# AIRZAI_LED_STRIP_FLEX_REVA_10mmPitch.net
KiCad netlist of a schematic drawn in Altium Designer
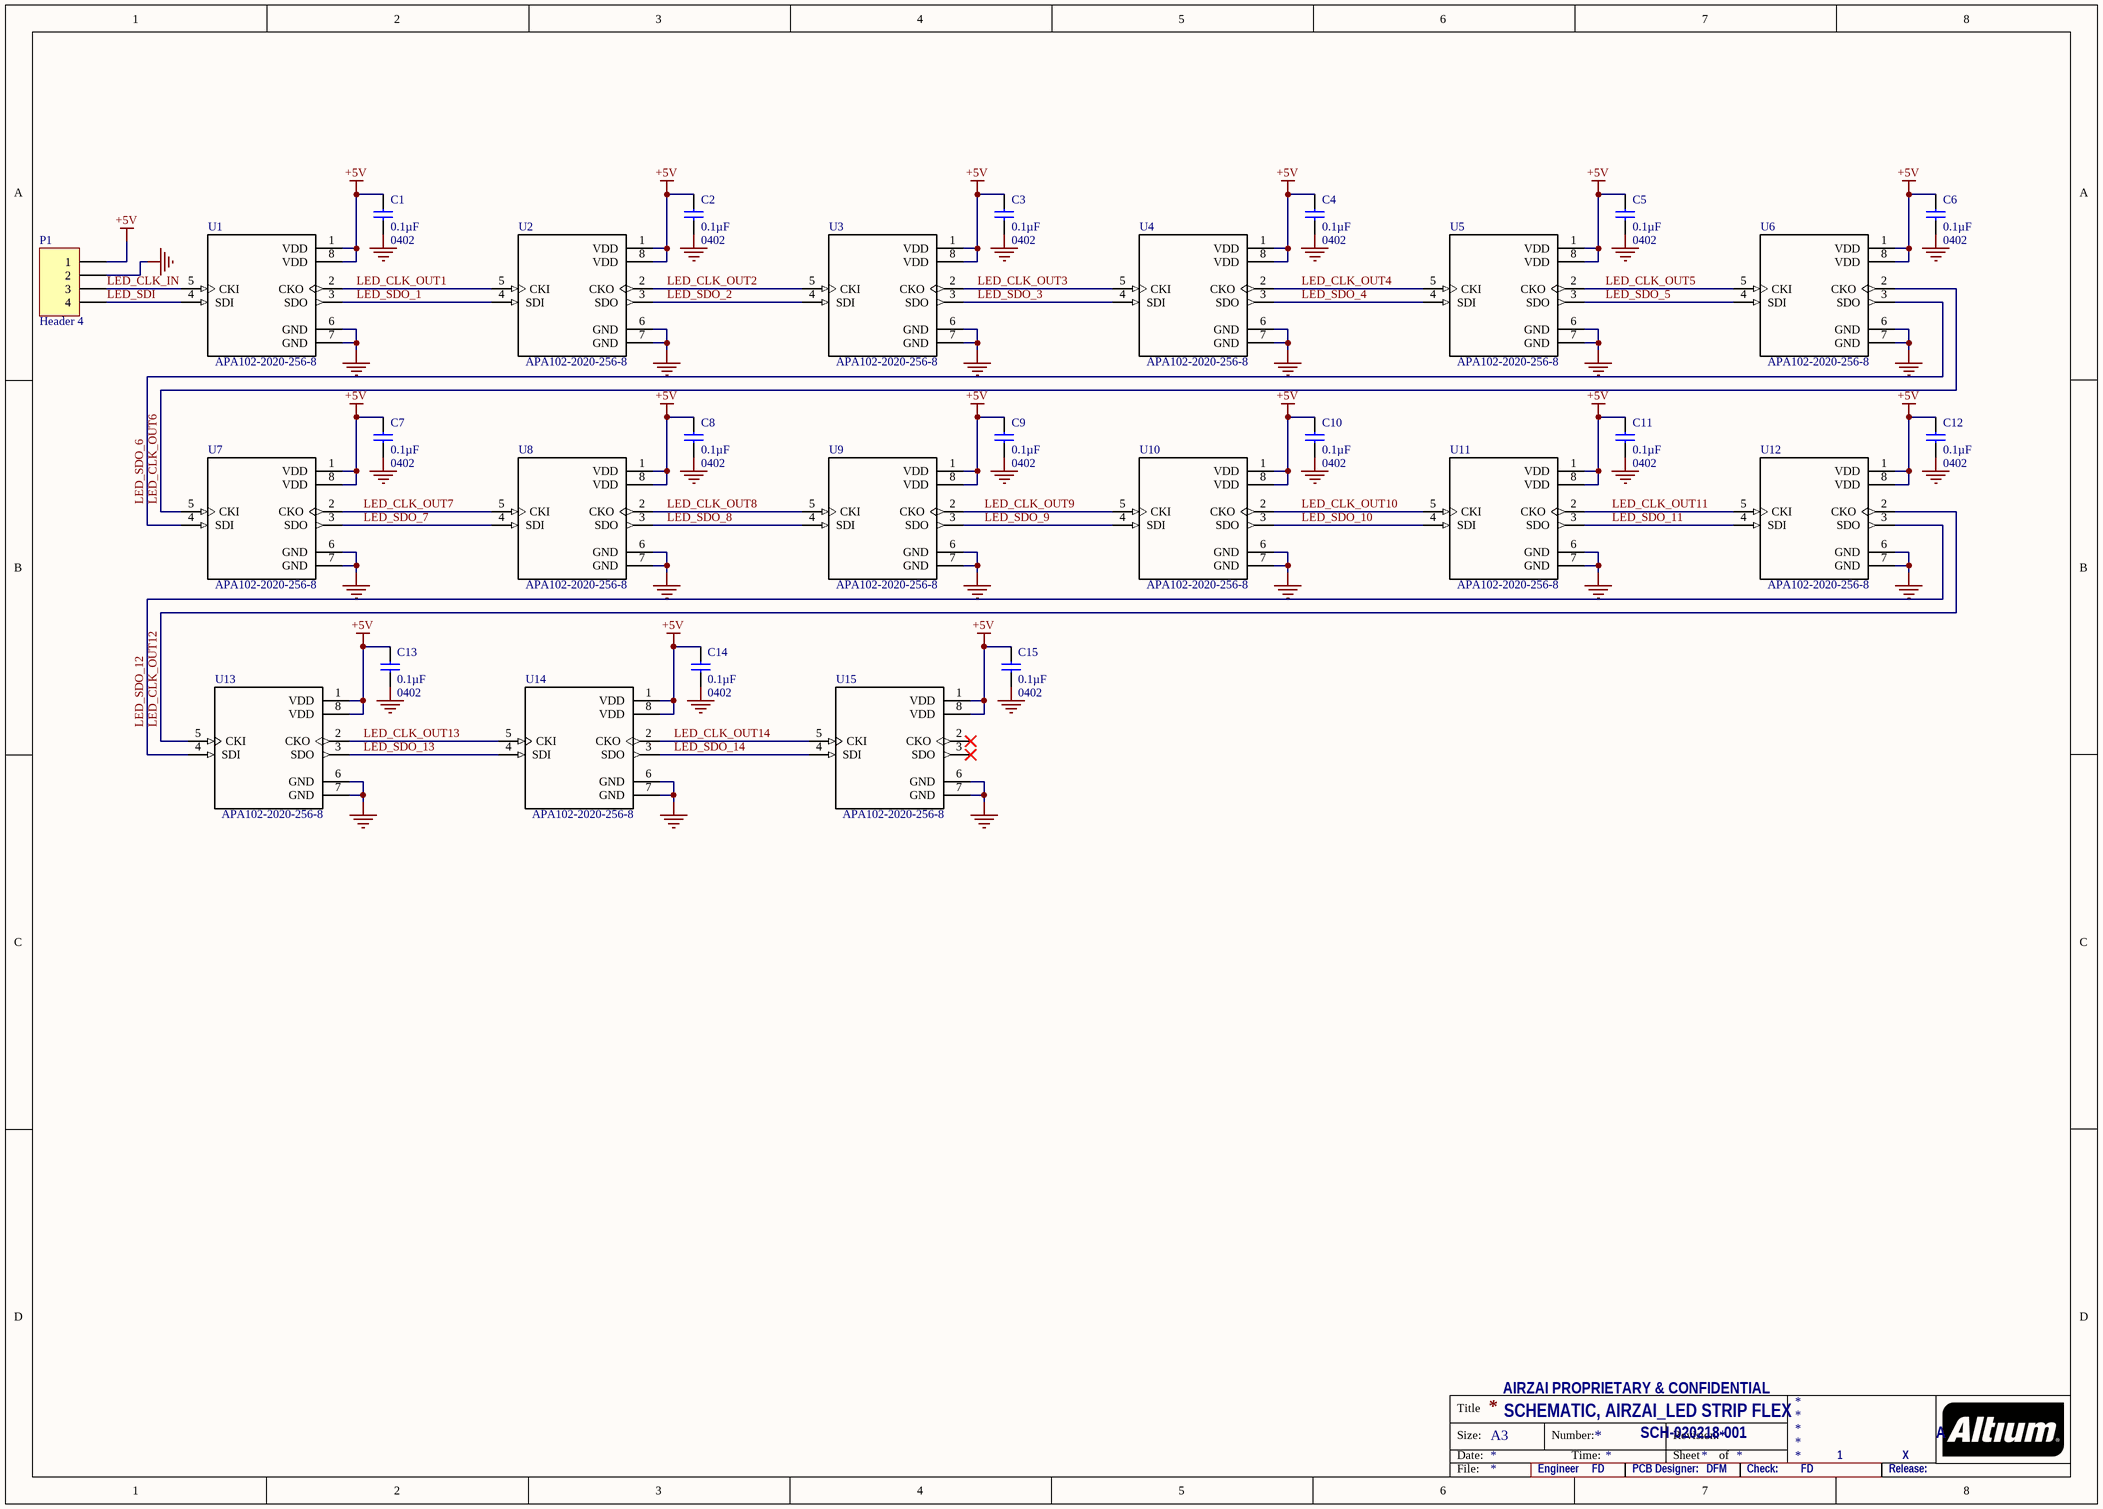
[diagram p0: AIRZAI_LED_STRIP_FLEX_REVA_10mmPitch.SchDoc]

(export (version "E")
  (design (tool "Eeschema 10.0.6"))
  (components
    (comp (ref "C1")
      (value "0.1µF")
      (footprint "0402")
      (description "Capacitor, X7R, ±10%")
      (fields (field (name "MANUFACTURER") "TDK") (field (name "MANUFACTURER PART NUMBER") "C1005X7R1C104K"))
      (libsource (lib "Nordic Passive DB") (part "CAP"))
    )
    (comp (ref "C2")
      (value "0.1µF")
      (footprint "0402")
      (description "Capacitor, X7R, ±10%")
      (fields (field (name "MANUFACTURER") "TDK") (field (name "MANUFACTURER PART NUMBER") "C1005X7R1C104K"))
      (libsource (lib "Nordic Passive DB") (part "CAP"))
    )
    (comp (ref "C3")
      (value "0.1µF")
      (footprint "0402")
      (description "Capacitor, X7R, ±10%")
      (fields (field (name "MANUFACTURER") "TDK") (field (name "MANUFACTURER PART NUMBER") "C1005X7R1C104K"))
      (libsource (lib "Nordic Passive DB") (part "CAP"))
    )
    (comp (ref "C4")
      (value "0.1µF")
      (footprint "0402")
      (description "Capacitor, X7R, ±10%")
      (fields (field (name "MANUFACTURER") "TDK") (field (name "MANUFACTURER PART NUMBER") "C1005X7R1C104K"))
      (libsource (lib "Nordic Passive DB") (part "CAP"))
    )
    (comp (ref "C5")
      (value "0.1µF")
      (footprint "0402")
      (description "Capacitor, X7R, ±10%")
      (fields (field (name "MANUFACTURER") "TDK") (field (name "MANUFACTURER PART NUMBER") "C1005X7R1C104K"))
      (libsource (lib "Nordic Passive DB") (part "CAP"))
    )
    (comp (ref "C6")
      (value "0.1µF")
      (footprint "0402")
      (description "Capacitor, X7R, ±10%")
      (fields (field (name "MANUFACTURER") "TDK") (field (name "MANUFACTURER PART NUMBER") "C1005X7R1C104K"))
      (libsource (lib "Nordic Passive DB") (part "CAP"))
    )
    (comp (ref "C7")
      (value "0.1µF")
      (footprint "0402")
      (description "Capacitor, X7R, ±10%")
      (fields (field (name "MANUFACTURER") "TDK") (field (name "MANUFACTURER PART NUMBER") "C1005X7R1C104K"))
      (libsource (lib "Nordic Passive DB") (part "CAP"))
    )
    (comp (ref "C8")
      (value "0.1µF")
      (footprint "0402")
      (description "Capacitor, X7R, ±10%")
      (fields (field (name "MANUFACTURER") "TDK") (field (name "MANUFACTURER PART NUMBER") "C1005X7R1C104K"))
      (libsource (lib "Nordic Passive DB") (part "CAP"))
    )
    (comp (ref "C9")
      (value "0.1µF")
      (footprint "0402")
      (description "Capacitor, X7R, ±10%")
      (fields (field (name "MANUFACTURER") "TDK") (field (name "MANUFACTURER PART NUMBER") "C1005X7R1C104K"))
      (libsource (lib "Nordic Passive DB") (part "CAP"))
    )
    (comp (ref "C10")
      (value "0.1µF")
      (footprint "0402")
      (description "Capacitor, X7R, ±10%")
      (fields (field (name "MANUFACTURER") "TDK") (field (name "MANUFACTURER PART NUMBER") "C1005X7R1C104K"))
      (libsource (lib "Nordic Passive DB") (part "CAP"))
    )
    (comp (ref "C11")
      (value "0.1µF")
      (footprint "0402")
      (description "Capacitor, X7R, ±10%")
      (fields (field (name "MANUFACTURER") "TDK") (field (name "MANUFACTURER PART NUMBER") "C1005X7R1C104K"))
      (libsource (lib "Nordic Passive DB") (part "CAP"))
    )
    (comp (ref "C12")
      (value "0.1µF")
      (footprint "0402")
      (description "Capacitor, X7R, ±10%")
      (fields (field (name "MANUFACTURER") "TDK") (field (name "MANUFACTURER PART NUMBER") "C1005X7R1C104K"))
      (libsource (lib "Nordic Passive DB") (part "CAP"))
    )
    (comp (ref "C13")
      (value "0.1µF")
      (footprint "0402")
      (description "Capacitor, X7R, ±10%")
      (fields (field (name "MANUFACTURER") "TDK") (field (name "MANUFACTURER PART NUMBER") "C1005X7R1C104K"))
      (libsource (lib "Nordic Passive DB") (part "CAP"))
    )
    (comp (ref "C14")
      (value "0.1µF")
      (footprint "0402")
      (description "Capacitor, X7R, ±10%")
      (fields (field (name "MANUFACTURER") "TDK") (field (name "MANUFACTURER PART NUMBER") "C1005X7R1C104K"))
      (libsource (lib "Nordic Passive DB") (part "CAP"))
    )
    (comp (ref "C15")
      (value "0.1µF")
      (footprint "0402")
      (description "Capacitor, X7R, ±10%")
      (fields (field (name "MANUFACTURER") "TDK") (field (name "MANUFACTURER PART NUMBER") "C1005X7R1C104K"))
      (libsource (lib "Nordic Passive DB") (part "CAP"))
    )
    (comp (ref "P1")
      (value "Header 4")
      (footprint "FFC_4Pads")
      (description "Header, 4-Pin")
      (fields (field (name "PUBLISHER") "Altium Limited"))
      (libsource (lib "Miscellaneous Connectors") (part "Header 4"))
    )
    (comp (ref "U1")
      (value "APA102-2020-256-8")
      (footprint "APA102–2020")
      (description "DotStar Micro LEDs")
      (fields (field (name "MF") "Adafruit Industries") (field (name "MP") "APA-102-2020-256-8"))
      (libsource (lib "AIRZAI_LED_SENSE_FLEX_REVA") (part "APA102-2020-256-8"))
    )
    (comp (ref "U2")
      (value "APA102-2020-256-8")
      (footprint "APA102–2020")
      (description "DotStar Micro LEDs")
      (fields (field (name "MF") "Adafruit Industries") (field (name "MP") "APA-102-2020-256-8"))
      (libsource (lib "AIRZAI_LED_SENSE_FLEX_REVA") (part "APA102-2020-256-8"))
    )
    (comp (ref "U3")
      (value "APA102-2020-256-8")
      (footprint "APA102–2020")
      (description "DotStar Micro LEDs")
      (fields (field (name "MF") "Adafruit Industries") (field (name "MP") "APA-102-2020-256-8"))
      (libsource (lib "AIRZAI_LED_SENSE_FLEX_REVA") (part "APA102-2020-256-8"))
    )
    (comp (ref "U4")
      (value "APA102-2020-256-8")
      (footprint "APA102–2020")
      (description "DotStar Micro LEDs")
      (fields (field (name "MF") "Adafruit Industries") (field (name "MP") "APA-102-2020-256-8"))
      (libsource (lib "AIRZAI_LED_SENSE_FLEX_REVA") (part "APA102-2020-256-8"))
    )
    (comp (ref "U5")
      (value "APA102-2020-256-8")
      (footprint "APA102–2020")
      (description "DotStar Micro LEDs")
      (fields (field (name "MF") "Adafruit Industries") (field (name "MP") "APA-102-2020-256-8"))
      (libsource (lib "AIRZAI_LED_SENSE_FLEX_REVA") (part "APA102-2020-256-8"))
    )
    (comp (ref "U6")
      (value "APA102-2020-256-8")
      (footprint "APA102–2020")
      (description "DotStar Micro LEDs")
      (fields (field (name "MF") "Adafruit Industries") (field (name "MP") "APA-102-2020-256-8"))
      (libsource (lib "AIRZAI_LED_SENSE_FLEX_REVA") (part "APA102-2020-256-8"))
    )
    (comp (ref "U7")
      (value "APA102-2020-256-8")
      (footprint "APA102–2020")
      (description "DotStar Micro LEDs")
      (fields (field (name "MF") "Adafruit Industries") (field (name "MP") "APA-102-2020-256-8"))
      (libsource (lib "AIRZAI_LED_SENSE_FLEX_REVA") (part "APA102-2020-256-8"))
    )
    (comp (ref "U8")
      (value "APA102-2020-256-8")
      (footprint "APA102–2020")
      (description "DotStar Micro LEDs")
      (fields (field (name "MF") "Adafruit Industries") (field (name "MP") "APA-102-2020-256-8"))
      (libsource (lib "AIRZAI_LED_SENSE_FLEX_REVA") (part "APA102-2020-256-8"))
    )
    (comp (ref "U9")
      (value "APA102-2020-256-8")
      (footprint "APA102–2020")
      (description "DotStar Micro LEDs")
      (fields (field (name "MF") "Adafruit Industries") (field (name "MP") "APA-102-2020-256-8"))
      (libsource (lib "AIRZAI_LED_SENSE_FLEX_REVA") (part "APA102-2020-256-8"))
    )
    (comp (ref "U10")
      (value "APA102-2020-256-8")
      (footprint "APA102–2020")
      (description "DotStar Micro LEDs")
      (fields (field (name "MF") "Adafruit Industries") (field (name "MP") "APA-102-2020-256-8"))
      (libsource (lib "AIRZAI_LED_SENSE_FLEX_REVA") (part "APA102-2020-256-8"))
    )
    (comp (ref "U11")
      (value "APA102-2020-256-8")
      (footprint "APA102–2020")
      (description "DotStar Micro LEDs")
      (fields (field (name "MF") "Adafruit Industries") (field (name "MP") "APA-102-2020-256-8"))
      (libsource (lib "AIRZAI_LED_SENSE_FLEX_REVA") (part "APA102-2020-256-8"))
    )
    (comp (ref "U12")
      (value "APA102-2020-256-8")
      (footprint "APA102–2020")
      (description "DotStar Micro LEDs")
      (fields (field (name "MF") "Adafruit Industries") (field (name "MP") "APA-102-2020-256-8"))
      (libsource (lib "AIRZAI_LED_SENSE_FLEX_REVA") (part "APA102-2020-256-8"))
    )
    (comp (ref "U13")
      (value "APA102-2020-256-8")
      (footprint "APA102–2020")
      (description "DotStar Micro LEDs")
      (fields (field (name "MF") "Adafruit Industries") (field (name "MP") "APA-102-2020-256-8"))
      (libsource (lib "AIRZAI_LED_SENSE_FLEX_REVA") (part "APA102-2020-256-8"))
    )
    (comp (ref "U14")
      (value "APA102-2020-256-8")
      (footprint "APA102–2020")
      (description "DotStar Micro LEDs")
      (fields (field (name "MF") "Adafruit Industries") (field (name "MP") "APA-102-2020-256-8"))
      (libsource (lib "AIRZAI_LED_SENSE_FLEX_REVA") (part "APA102-2020-256-8"))
    )
    (comp (ref "U15")
      (value "APA102-2020-256-8")
      (footprint "APA102–2020")
      (description "DotStar Micro LEDs")
      (fields (field (name "MF") "Adafruit Industries") (field (name "MP") "APA-102-2020-256-8"))
      (libsource (lib "AIRZAI_LED_SENSE_FLEX_REVA") (part "APA102-2020-256-8"))
    )
  )
  (nets
    (net (code "1") (name "+5V") (class "Default")
      (node (ref "C1") (pin "1") (pinfunction "1_1") (pintype "passive"))
      (node (ref "C10") (pin "1") (pinfunction "1_1") (pintype "passive"))
      (node (ref "C11") (pin "1") (pinfunction "1_1") (pintype "passive"))
      (node (ref "C12") (pin "1") (pinfunction "1_1") (pintype "passive"))
      (node (ref "C13") (pin "1") (pinfunction "1_1") (pintype "passive"))
      (node (ref "C14") (pin "1") (pinfunction "1_1") (pintype "passive"))
      (node (ref "C15") (pin "1") (pinfunction "1_1") (pintype "passive"))
      (node (ref "C2") (pin "1") (pinfunction "1_1") (pintype "passive"))
      (node (ref "C3") (pin "1") (pinfunction "1_1") (pintype "passive"))
      (node (ref "C4") (pin "1") (pinfunction "1_1") (pintype "passive"))
      (node (ref "C5") (pin "1") (pinfunction "1_1") (pintype "passive"))
      (node (ref "C6") (pin "1") (pinfunction "1_1") (pintype "passive"))
      (node (ref "C7") (pin "1") (pinfunction "1_1") (pintype "passive"))
      (node (ref "C8") (pin "1") (pinfunction "1_1") (pintype "passive"))
      (node (ref "C9") (pin "1") (pinfunction "1_1") (pintype "passive"))
      (node (ref "P1") (pin "1") (pinfunction "1_1") (pintype "passive"))
      (node (ref "U1") (pin "1") (pinfunction "VDD_1") (pintype "power_in"))
      (node (ref "U1") (pin "8") (pinfunction "VDD_8") (pintype "power_in"))
      (node (ref "U10") (pin "1") (pinfunction "VDD_1") (pintype "power_in"))
      (node (ref "U10") (pin "8") (pinfunction "VDD_8") (pintype "power_in"))
      (node (ref "U11") (pin "1") (pinfunction "VDD_1") (pintype "power_in"))
      (node (ref "U11") (pin "8") (pinfunction "VDD_8") (pintype "power_in"))
      (node (ref "U12") (pin "1") (pinfunction "VDD_1") (pintype "power_in"))
      (node (ref "U12") (pin "8") (pinfunction "VDD_8") (pintype "power_in"))
      (node (ref "U13") (pin "1") (pinfunction "VDD_1") (pintype "power_in"))
      (node (ref "U13") (pin "8") (pinfunction "VDD_8") (pintype "power_in"))
      (node (ref "U14") (pin "1") (pinfunction "VDD_1") (pintype "power_in"))
      (node (ref "U14") (pin "8") (pinfunction "VDD_8") (pintype "power_in"))
      (node (ref "U15") (pin "1") (pinfunction "VDD_1") (pintype "power_in"))
      (node (ref "U15") (pin "8") (pinfunction "VDD_8") (pintype "power_in"))
      (node (ref "U2") (pin "1") (pinfunction "VDD_1") (pintype "power_in"))
      (node (ref "U2") (pin "8") (pinfunction "VDD_8") (pintype "power_in"))
      (node (ref "U3") (pin "1") (pinfunction "VDD_1") (pintype "power_in"))
      (node (ref "U3") (pin "8") (pinfunction "VDD_8") (pintype "power_in"))
      (node (ref "U4") (pin "1") (pinfunction "VDD_1") (pintype "power_in"))
      (node (ref "U4") (pin "8") (pinfunction "VDD_8") (pintype "power_in"))
      (node (ref "U5") (pin "1") (pinfunction "VDD_1") (pintype "power_in"))
      (node (ref "U5") (pin "8") (pinfunction "VDD_8") (pintype "power_in"))
      (node (ref "U6") (pin "1") (pinfunction "VDD_1") (pintype "power_in"))
      (node (ref "U6") (pin "8") (pinfunction "VDD_8") (pintype "power_in"))
      (node (ref "U7") (pin "1") (pinfunction "VDD_1") (pintype "power_in"))
      (node (ref "U7") (pin "8") (pinfunction "VDD_8") (pintype "power_in"))
      (node (ref "U8") (pin "1") (pinfunction "VDD_1") (pintype "power_in"))
      (node (ref "U8") (pin "8") (pinfunction "VDD_8") (pintype "power_in"))
      (node (ref "U9") (pin "1") (pinfunction "VDD_1") (pintype "power_in"))
      (node (ref "U9") (pin "8") (pinfunction "VDD_8") (pintype "power_in"))
    )
    (net (code "2") (name "/LED_CLK_IN") (class "Default")
      (node (ref "P1") (pin "3") (pinfunction "3_3") (pintype "passive"))
      (node (ref "U1") (pin "5") (pinfunction "CKI_5") (pintype "input"))
    )
    (net (code "3") (name "/LED_CLK_OUT1") (class "Default")
      (node (ref "U1") (pin "2") (pinfunction "CKO_2") (pintype "output"))
      (node (ref "U2") (pin "5") (pinfunction "CKI_5") (pintype "input"))
    )
    (net (code "4") (name "/LED_CLK_OUT2") (class "Default")
      (node (ref "U2") (pin "2") (pinfunction "CKO_2") (pintype "output"))
      (node (ref "U3") (pin "5") (pinfunction "CKI_5") (pintype "input"))
    )
    (net (code "5") (name "/LED_CLK_OUT3") (class "Default")
      (node (ref "U3") (pin "2") (pinfunction "CKO_2") (pintype "output"))
      (node (ref "U4") (pin "5") (pinfunction "CKI_5") (pintype "input"))
    )
    (net (code "6") (name "/LED_CLK_OUT4") (class "Default")
      (node (ref "U4") (pin "2") (pinfunction "CKO_2") (pintype "output"))
      (node (ref "U5") (pin "5") (pinfunction "CKI_5") (pintype "input"))
    )
    (net (code "7") (name "/LED_CLK_OUT5") (class "Default")
      (node (ref "U5") (pin "2") (pinfunction "CKO_2") (pintype "output"))
      (node (ref "U6") (pin "5") (pinfunction "CKI_5") (pintype "input"))
    )
    (net (code "8") (name "/LED_CLK_OUT6") (class "Default")
      (node (ref "U6") (pin "2") (pinfunction "CKO_2") (pintype "output"))
      (node (ref "U7") (pin "5") (pinfunction "CKI_5") (pintype "input"))
    )
    (net (code "9") (name "/LED_CLK_OUT7") (class "Default")
      (node (ref "U7") (pin "2") (pinfunction "CKO_2") (pintype "output"))
      (node (ref "U8") (pin "5") (pinfunction "CKI_5") (pintype "input"))
    )
    (net (code "10") (name "/LED_CLK_OUT8") (class "Default")
      (node (ref "U8") (pin "2") (pinfunction "CKO_2") (pintype "output"))
      (node (ref "U9") (pin "5") (pinfunction "CKI_5") (pintype "input"))
    )
    (net (code "11") (name "/LED_CLK_OUT9") (class "Default")
      (node (ref "U10") (pin "5") (pinfunction "CKI_5") (pintype "input"))
      (node (ref "U9") (pin "2") (pinfunction "CKO_2") (pintype "output"))
    )
    (net (code "12") (name "/LED_CLK_OUT10") (class "Default")
      (node (ref "U10") (pin "2") (pinfunction "CKO_2") (pintype "output"))
      (node (ref "U11") (pin "5") (pinfunction "CKI_5") (pintype "input"))
    )
    (net (code "13") (name "/LED_CLK_OUT11") (class "Default")
      (node (ref "U11") (pin "2") (pinfunction "CKO_2") (pintype "output"))
      (node (ref "U12") (pin "5") (pinfunction "CKI_5") (pintype "input"))
    )
    (net (code "14") (name "/LED_CLK_OUT12") (class "Default")
      (node (ref "U12") (pin "2") (pinfunction "CKO_2") (pintype "output"))
      (node (ref "U13") (pin "5") (pinfunction "CKI_5") (pintype "input"))
    )
    (net (code "15") (name "/LED_CLK_OUT13") (class "Default")
      (node (ref "U13") (pin "2") (pinfunction "CKO_2") (pintype "output"))
      (node (ref "U14") (pin "5") (pinfunction "CKI_5") (pintype "input"))
    )
    (net (code "16") (name "/LED_CLK_OUT14") (class "Default")
      (node (ref "U14") (pin "2") (pinfunction "CKO_2") (pintype "output"))
      (node (ref "U15") (pin "5") (pinfunction "CKI_5") (pintype "input"))
    )
    (net (code "17") (name "/LED_SDI") (class "Default")
      (node (ref "P1") (pin "4") (pinfunction "4_4") (pintype "passive"))
      (node (ref "U1") (pin "4") (pinfunction "SDI_4") (pintype "input"))
    )
    (net (code "18") (name "/LED_SDO_1") (class "Default")
      (node (ref "U1") (pin "3") (pinfunction "SDO_3") (pintype "output"))
      (node (ref "U2") (pin "4") (pinfunction "SDI_4") (pintype "input"))
    )
    (net (code "19") (name "/LED_SDO_2") (class "Default")
      (node (ref "U2") (pin "3") (pinfunction "SDO_3") (pintype "output"))
      (node (ref "U3") (pin "4") (pinfunction "SDI_4") (pintype "input"))
    )
    (net (code "20") (name "/LED_SDO_3") (class "Default")
      (node (ref "U3") (pin "3") (pinfunction "SDO_3") (pintype "output"))
      (node (ref "U4") (pin "4") (pinfunction "SDI_4") (pintype "input"))
    )
    (net (code "21") (name "/LED_SDO_4") (class "Default")
      (node (ref "U4") (pin "3") (pinfunction "SDO_3") (pintype "output"))
      (node (ref "U5") (pin "4") (pinfunction "SDI_4") (pintype "input"))
    )
    (net (code "22") (name "/LED_SDO_5") (class "Default")
      (node (ref "U5") (pin "3") (pinfunction "SDO_3") (pintype "output"))
      (node (ref "U6") (pin "4") (pinfunction "SDI_4") (pintype "input"))
    )
    (net (code "23") (name "/LED_SDO_6") (class "Default")
      (node (ref "U6") (pin "3") (pinfunction "SDO_3") (pintype "output"))
      (node (ref "U7") (pin "4") (pinfunction "SDI_4") (pintype "input"))
    )
    (net (code "24") (name "/LED_SDO_7") (class "Default")
      (node (ref "U7") (pin "3") (pinfunction "SDO_3") (pintype "output"))
      (node (ref "U8") (pin "4") (pinfunction "SDI_4") (pintype "input"))
    )
    (net (code "25") (name "/LED_SDO_8") (class "Default")
      (node (ref "U8") (pin "3") (pinfunction "SDO_3") (pintype "output"))
      (node (ref "U9") (pin "4") (pinfunction "SDI_4") (pintype "input"))
    )
    (net (code "26") (name "/LED_SDO_9") (class "Default")
      (node (ref "U10") (pin "4") (pinfunction "SDI_4") (pintype "input"))
      (node (ref "U9") (pin "3") (pinfunction "SDO_3") (pintype "output"))
    )
    (net (code "27") (name "/LED_SDO_10") (class "Default")
      (node (ref "U10") (pin "3") (pinfunction "SDO_3") (pintype "output"))
      (node (ref "U11") (pin "4") (pinfunction "SDI_4") (pintype "input"))
    )
    (net (code "28") (name "/LED_SDO_11") (class "Default")
      (node (ref "U11") (pin "3") (pinfunction "SDO_3") (pintype "output"))
      (node (ref "U12") (pin "4") (pinfunction "SDI_4") (pintype "input"))
    )
    (net (code "29") (name "/LED_SDO_12") (class "Default")
      (node (ref "U12") (pin "3") (pinfunction "SDO_3") (pintype "output"))
      (node (ref "U13") (pin "4") (pinfunction "SDI_4") (pintype "input"))
    )
    (net (code "30") (name "/LED_SDO_13") (class "Default")
      (node (ref "U13") (pin "3") (pinfunction "SDO_3") (pintype "output"))
      (node (ref "U14") (pin "4") (pinfunction "SDI_4") (pintype "input"))
    )
    (net (code "31") (name "/LED_SDO_14") (class "Default")
      (node (ref "U14") (pin "3") (pinfunction "SDO_3") (pintype "output"))
      (node (ref "U15") (pin "4") (pinfunction "SDI_4") (pintype "input"))
    )
    (net (code "32") (name "GND") (class "Default")
      (node (ref "C1") (pin "2") (pinfunction "2_2") (pintype "passive"))
      (node (ref "C10") (pin "2") (pinfunction "2_2") (pintype "passive"))
      (node (ref "C11") (pin "2") (pinfunction "2_2") (pintype "passive"))
      (node (ref "C12") (pin "2") (pinfunction "2_2") (pintype "passive"))
      (node (ref "C13") (pin "2") (pinfunction "2_2") (pintype "passive"))
      (node (ref "C14") (pin "2") (pinfunction "2_2") (pintype "passive"))
      (node (ref "C15") (pin "2") (pinfunction "2_2") (pintype "passive"))
      (node (ref "C2") (pin "2") (pinfunction "2_2") (pintype "passive"))
      (node (ref "C3") (pin "2") (pinfunction "2_2") (pintype "passive"))
      (node (ref "C4") (pin "2") (pinfunction "2_2") (pintype "passive"))
      (node (ref "C5") (pin "2") (pinfunction "2_2") (pintype "passive"))
      (node (ref "C6") (pin "2") (pinfunction "2_2") (pintype "passive"))
      (node (ref "C7") (pin "2") (pinfunction "2_2") (pintype "passive"))
      (node (ref "C8") (pin "2") (pinfunction "2_2") (pintype "passive"))
      (node (ref "C9") (pin "2") (pinfunction "2_2") (pintype "passive"))
      (node (ref "P1") (pin "2") (pinfunction "2_2") (pintype "passive"))
      (node (ref "U1") (pin "6") (pinfunction "GND_6") (pintype "power_in"))
      (node (ref "U1") (pin "7") (pinfunction "GND_7") (pintype "power_in"))
      (node (ref "U10") (pin "6") (pinfunction "GND_6") (pintype "power_in"))
      (node (ref "U10") (pin "7") (pinfunction "GND_7") (pintype "power_in"))
      (node (ref "U11") (pin "6") (pinfunction "GND_6") (pintype "power_in"))
      (node (ref "U11") (pin "7") (pinfunction "GND_7") (pintype "power_in"))
      (node (ref "U12") (pin "6") (pinfunction "GND_6") (pintype "power_in"))
      (node (ref "U12") (pin "7") (pinfunction "GND_7") (pintype "power_in"))
      (node (ref "U13") (pin "6") (pinfunction "GND_6") (pintype "power_in"))
      (node (ref "U13") (pin "7") (pinfunction "GND_7") (pintype "power_in"))
      (node (ref "U14") (pin "6") (pinfunction "GND_6") (pintype "power_in"))
      (node (ref "U14") (pin "7") (pinfunction "GND_7") (pintype "power_in"))
      (node (ref "U15") (pin "6") (pinfunction "GND_6") (pintype "power_in"))
      (node (ref "U15") (pin "7") (pinfunction "GND_7") (pintype "power_in"))
      (node (ref "U2") (pin "6") (pinfunction "GND_6") (pintype "power_in"))
      (node (ref "U2") (pin "7") (pinfunction "GND_7") (pintype "power_in"))
      (node (ref "U3") (pin "6") (pinfunction "GND_6") (pintype "power_in"))
      (node (ref "U3") (pin "7") (pinfunction "GND_7") (pintype "power_in"))
      (node (ref "U4") (pin "6") (pinfunction "GND_6") (pintype "power_in"))
      (node (ref "U4") (pin "7") (pinfunction "GND_7") (pintype "power_in"))
      (node (ref "U5") (pin "6") (pinfunction "GND_6") (pintype "power_in"))
      (node (ref "U5") (pin "7") (pinfunction "GND_7") (pintype "power_in"))
      (node (ref "U6") (pin "6") (pinfunction "GND_6") (pintype "power_in"))
      (node (ref "U6") (pin "7") (pinfunction "GND_7") (pintype "power_in"))
      (node (ref "U7") (pin "6") (pinfunction "GND_6") (pintype "power_in"))
      (node (ref "U7") (pin "7") (pinfunction "GND_7") (pintype "power_in"))
      (node (ref "U8") (pin "6") (pinfunction "GND_6") (pintype "power_in"))
      (node (ref "U8") (pin "7") (pinfunction "GND_7") (pintype "power_in"))
      (node (ref "U9") (pin "6") (pinfunction "GND_6") (pintype "power_in"))
      (node (ref "U9") (pin "7") (pinfunction "GND_7") (pintype "power_in"))
    )
    (net (code "33") (name "unconnected-(U15-CKO-Pad2)") (class "Default")
      (node (ref "U15") (pin "2") (pinfunction "CKO_2") (pintype "output+no_connect"))
    )
    (net (code "34") (name "unconnected-(U15-SDO-Pad3)") (class "Default")
      (node (ref "U15") (pin "3") (pinfunction "SDO_3") (pintype "output+no_connect"))
    )
  )
)
